# SparkFun_CP2103_Breakout.net
KiCad netlist of a schematic drawn in EAGLE
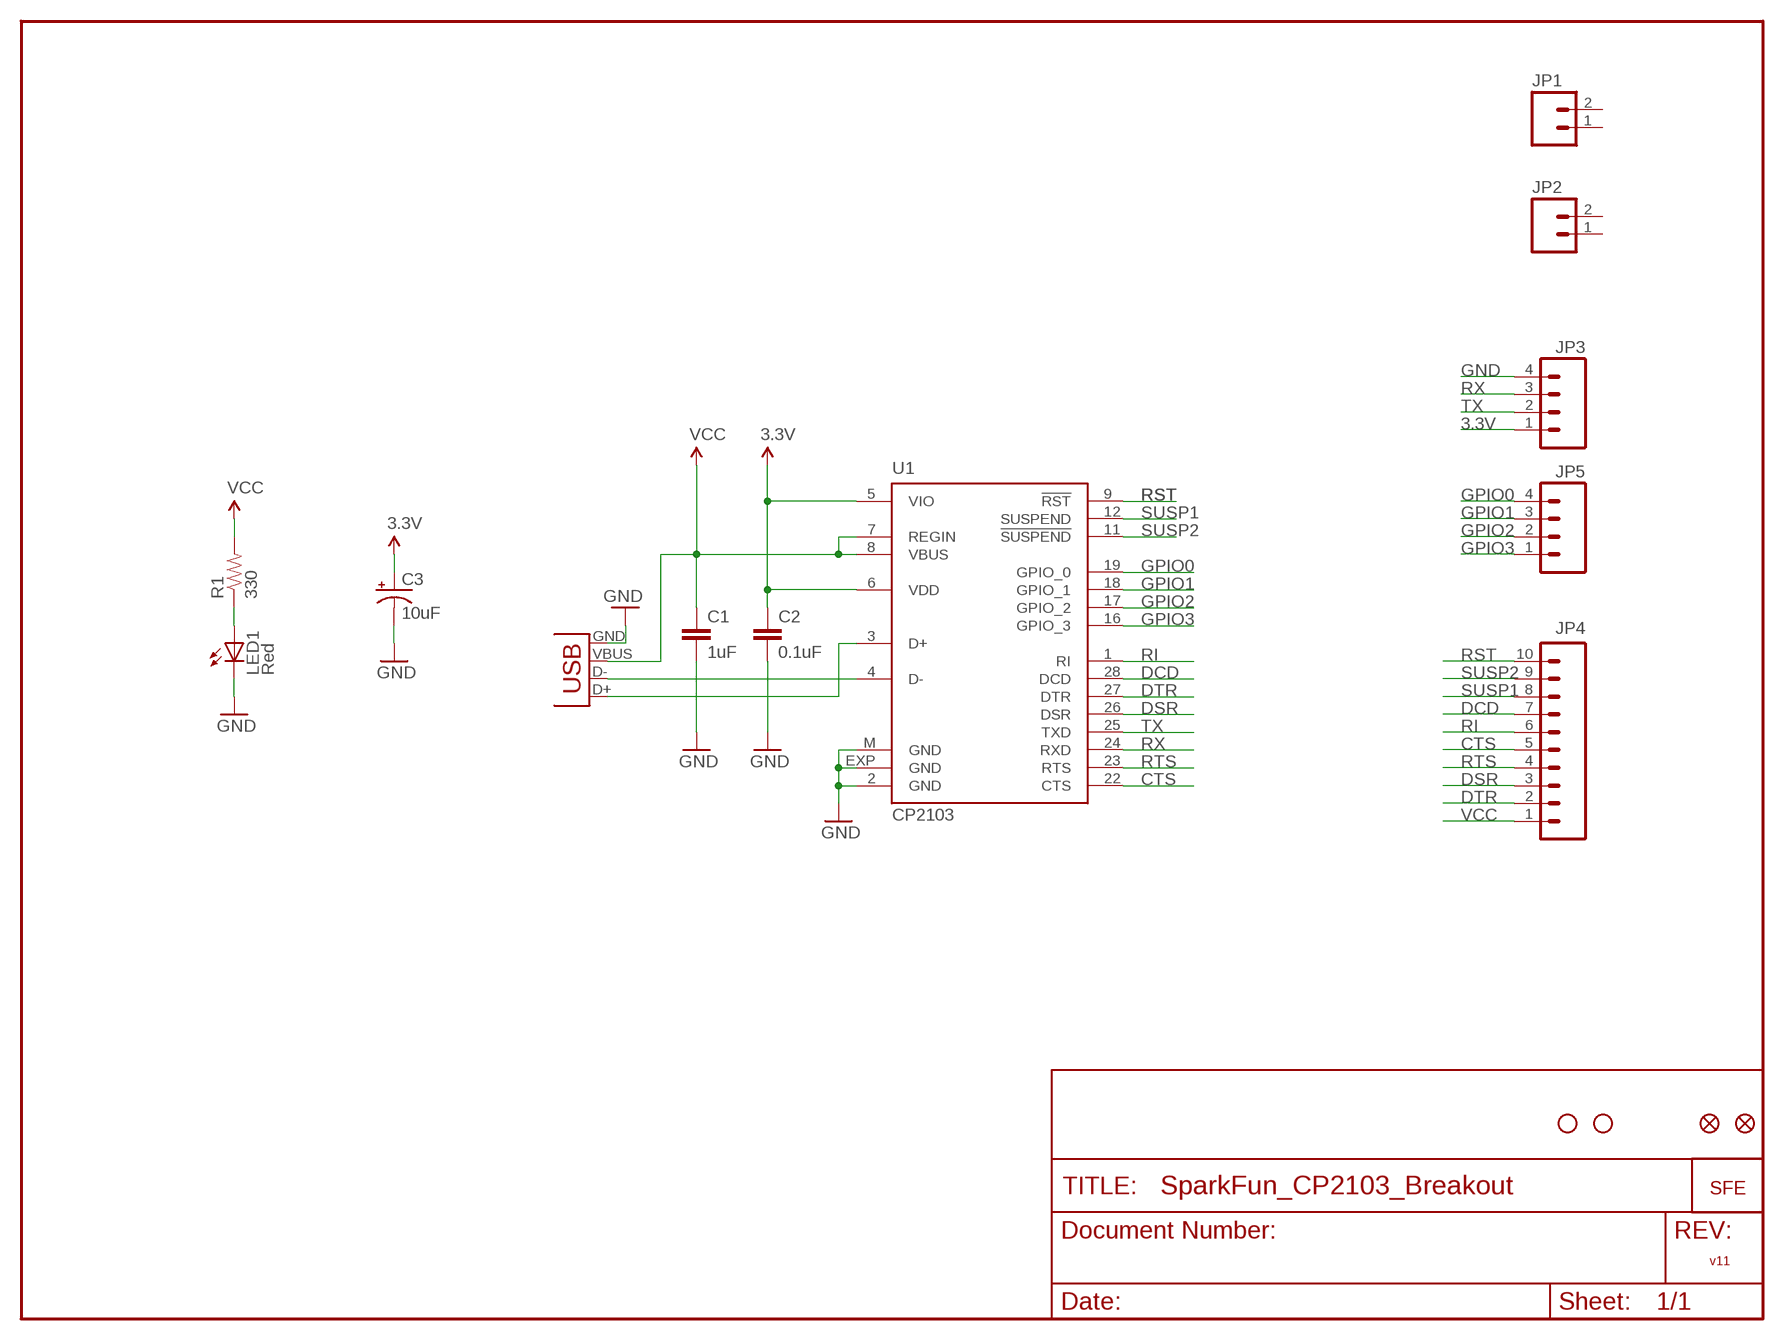
[diagram p0: schematic, sheet 1]

(export (version "E")
  (design (tool "Eeschema 10.0.6"))
  (components
    (comp (ref "C1")
      (value "1uF")
      (footprint "eagle-import:C0402")
      (libsource (lib "eagle-import") (part "CAP0402"))
    )
    (comp (ref "C2")
      (value "0.1uF")
      (footprint "eagle-import:C0402")
      (libsource (lib "eagle-import") (part "CAP0402"))
    )
    (comp (ref "C3")
      (value "10uF")
      (footprint "eagle-import:EIA3216")
      (libsource (lib "eagle-import") (part "CAP_POL1206"))
    )
    (comp (ref "JP1")
      (value "M02PTH")
      (footprint "eagle-import:1X02")
      (libsource (lib "eagle-import") (part "M02PTH"))
    )
    (comp (ref "JP2")
      (value "M02PTH")
      (footprint "eagle-import:1X02")
      (libsource (lib "eagle-import") (part "M02PTH"))
    )
    (comp (ref "JP3")
      (value "M04PTH")
      (footprint "eagle-import:1X04")
      (libsource (lib "eagle-import") (part "M04PTH"))
    )
    (comp (ref "JP4")
      (value "M100.1")
      (footprint "eagle-import:1X10")
      (libsource (lib "eagle-import") (part "M100.1"))
    )
    (comp (ref "JP5")
      (value "M04PTH")
      (footprint "eagle-import:1X04")
      (libsource (lib "eagle-import") (part "M04PTH"))
    )
    (comp (ref "LED1")
      (value "Red")
      (footprint "eagle-import:LED-1206")
      (libsource (lib "eagle-import") (part "LED1206"))
    )
    (comp (ref "R1")
      (value "330")
      (footprint "eagle-import:C0402")
      (libsource (lib "eagle-import") (part "RESISTOR0402"))
    )
    (comp (ref "U$1")
      (value "LOGO-SFENEW")
      (footprint "eagle-import:SFE-NEW-WEBLOGO")
      (libsource (lib "eagle-import") (part "LOGO-SFENEW"))
    )
    (comp (ref "U$2")
      (value "FIDUCIAL1X2")
      (footprint "eagle-import:FIDUCIAL-1X2")
      (libsource (lib "eagle-import") (part "FIDUCIAL1X2"))
    )
    (comp (ref "U$3")
      (value "FIDUCIAL1X2")
      (footprint "eagle-import:FIDUCIAL-1X2")
      (libsource (lib "eagle-import") (part "FIDUCIAL1X2"))
    )
    (comp (ref "U$6")
      (value "STAND-OFF")
      (footprint "eagle-import:STAND-OFF")
      (libsource (lib "eagle-import") (part "STAND-OFF"))
    )
    (comp (ref "U$7")
      (value "STAND-OFF")
      (footprint "eagle-import:STAND-OFF")
      (libsource (lib "eagle-import") (part "STAND-OFF"))
    )
    (comp (ref "U1")
      (value "CP2103")
      (footprint "eagle-import:MLP28")
      (libsource (lib "eagle-import") (part "CP2103_USB_UART"))
    )
    (comp (ref "X1")
      (value "USBPTH")
      (footprint "eagle-import:USB-B-PTH")
      (libsource (lib "eagle-import") (part "USBPTH"))
    )
  )
  (nets
    (net (code "1") (name "/CTS") (class "Default")
      (node (ref "JP4") (pin "5") (pinfunction "5_5") (pintype "passive"))
      (node (ref "U1") (pin "22") (pinfunction "CTS_22") (pintype "input"))
    )
    (net (code "2") (name "/DCD") (class "Default")
      (node (ref "JP4") (pin "7") (pinfunction "7_7") (pintype "passive"))
      (node (ref "U1") (pin "28") (pinfunction "DCD_28") (pintype "input"))
    )
    (net (code "3") (name "/DSR") (class "Default")
      (node (ref "JP4") (pin "3") (pinfunction "3_3") (pintype "passive"))
      (node (ref "U1") (pin "26") (pinfunction "DSR_26") (pintype "input"))
    )
    (net (code "4") (name "/DTR") (class "Default")
      (node (ref "JP4") (pin "2") (pinfunction "2_2") (pintype "passive"))
      (node (ref "U1") (pin "27") (pinfunction "DTR_27") (pintype "output"))
    )
    (net (code "5") (name "/GPIO0") (class "Default")
      (node (ref "JP5") (pin "4") (pinfunction "4_4") (pintype "passive"))
      (node (ref "U1") (pin "19") (pinfunction "GPIO_0_19") (pintype "bidirectional"))
    )
    (net (code "6") (name "/GPIO1") (class "Default")
      (node (ref "JP5") (pin "3") (pinfunction "3_3") (pintype "passive"))
      (node (ref "U1") (pin "18") (pinfunction "GPIO_1_18") (pintype "bidirectional"))
    )
    (net (code "7") (name "/GPIO2") (class "Default")
      (node (ref "JP5") (pin "2") (pinfunction "2_2") (pintype "passive"))
      (node (ref "U1") (pin "17") (pinfunction "GPIO_2_17") (pintype "bidirectional"))
    )
    (net (code "8") (name "/GPIO3") (class "Default")
      (node (ref "JP5") (pin "1") (pinfunction "1_1") (pintype "passive"))
      (node (ref "U1") (pin "16") (pinfunction "GPIO_3_16") (pintype "bidirectional"))
    )
    (net (code "9") (name "/RI") (class "Default")
      (node (ref "JP4") (pin "6") (pinfunction "6_6") (pintype "passive"))
      (node (ref "U1") (pin "1") (pinfunction "RI_1") (pintype "input"))
    )
    (net (code "10") (name "/RST") (class "Default")
      (node (ref "JP4") (pin "10") (pinfunction "10_10") (pintype "passive"))
      (node (ref "U1") (pin "9") (pinfunction "~{RST}_9") (pintype "bidirectional"))
    )
    (net (code "11") (name "/RTS") (class "Default")
      (node (ref "JP4") (pin "4") (pinfunction "4_4") (pintype "passive"))
      (node (ref "U1") (pin "23") (pinfunction "RTS_23") (pintype "output"))
    )
    (net (code "12") (name "/RX") (class "Default")
      (node (ref "JP3") (pin "3") (pinfunction "3_3") (pintype "passive"))
      (node (ref "U1") (pin "24") (pinfunction "RXD_24") (pintype "input"))
    )
    (net (code "13") (name "/SUSP1") (class "Default")
      (node (ref "JP4") (pin "8") (pinfunction "8_8") (pintype "passive"))
      (node (ref "U1") (pin "12") (pinfunction "SUSPEND_12") (pintype "output"))
    )
    (net (code "14") (name "/SUSP2") (class "Default")
      (node (ref "JP4") (pin "9") (pinfunction "9_9") (pintype "passive"))
      (node (ref "U1") (pin "11") (pinfunction "~{SUSPEND}_11") (pintype "output"))
    )
    (net (code "15") (name "/TX") (class "Default")
      (node (ref "JP3") (pin "2") (pinfunction "2_2") (pintype "passive"))
      (node (ref "U1") (pin "25") (pinfunction "TXD_25") (pintype "output"))
    )
    (net (code "16") (name "3.3V") (class "Default")
      (node (ref "C2") (pin "1") (pinfunction "1_1") (pintype "passive"))
      (node (ref "C3") (pin "A") (pinfunction "+_A") (pintype "passive"))
      (node (ref "JP3") (pin "1") (pinfunction "1_1") (pintype "passive"))
      (node (ref "U1") (pin "5") (pinfunction "VIO_5") (pintype "power_in"))
      (node (ref "U1") (pin "6") (pinfunction "VDD_6") (pintype "power_in"))
    )
    (net (code "17") (name "GND") (class "Default")
      (node (ref "C1") (pin "2") (pinfunction "2_2") (pintype "passive"))
      (node (ref "C2") (pin "2") (pinfunction "2_2") (pintype "passive"))
      (node (ref "C3") (pin "C") (pinfunction "-_C") (pintype "passive"))
      (node (ref "JP3") (pin "4") (pinfunction "4_4") (pintype "passive"))
      (node (ref "LED1") (pin "C") (pinfunction "C_C") (pintype "passive"))
      (node (ref "U1") (pin "2") (pinfunction "GND_2") (pintype "power_in"))
      (node (ref "U1") (pin "EXP") (pinfunction "GND_EXP") (pintype "power_in"))
      (node (ref "U1") (pin "M") (pinfunction "GND_M") (pintype "power_in"))
      (node (ref "X1") (pin "GND") (pinfunction "GND_GND") (pintype "bidirectional"))
    )
    (net (code "18") (name "Net-(LED1-PadA)") (class "Default")
      (node (ref "LED1") (pin "A") (pinfunction "A_A") (pintype "passive"))
      (node (ref "R1") (pin "1") (pinfunction "1_1") (pintype "passive"))
    )
    (net (code "19") (name "Net-(U1-D+)") (class "Default")
      (node (ref "U1") (pin "3") (pinfunction "D+_3") (pintype "bidirectional"))
      (node (ref "X1") (pin "D+") (pinfunction "D+_D+") (pintype "bidirectional"))
    )
    (net (code "20") (name "Net-(U1-D-)") (class "Default")
      (node (ref "U1") (pin "4") (pinfunction "D-_4") (pintype "bidirectional"))
      (node (ref "X1") (pin "D-") (pinfunction "D-_D-") (pintype "bidirectional"))
    )
    (net (code "21") (name "VCC") (class "Default")
      (node (ref "C1") (pin "1") (pinfunction "1_1") (pintype "passive"))
      (node (ref "JP4") (pin "1") (pinfunction "1_1") (pintype "passive"))
      (node (ref "R1") (pin "2") (pinfunction "2_2") (pintype "passive"))
      (node (ref "U1") (pin "7") (pinfunction "REGIN_7") (pintype "passive"))
      (node (ref "U1") (pin "8") (pinfunction "VBUS_8") (pintype "input"))
      (node (ref "X1") (pin "VBUS") (pinfunction "VBUS_VBUS") (pintype "bidirectional"))
    )
    (net (code "22") (name "unconnected-(JP1-Pad1)") (class "Default")
      (node (ref "JP1") (pin "1") (pinfunction "1_1") (pintype "passive"))
    )
    (net (code "23") (name "unconnected-(JP1-Pad2)") (class "Default")
      (node (ref "JP1") (pin "2") (pinfunction "2_2") (pintype "passive"))
    )
    (net (code "24") (name "unconnected-(JP2-Pad1)") (class "Default")
      (node (ref "JP2") (pin "1") (pinfunction "1_1") (pintype "passive"))
    )
    (net (code "25") (name "unconnected-(JP2-Pad2)") (class "Default")
      (node (ref "JP2") (pin "2") (pinfunction "2_2") (pintype "passive"))
    )
  )
)
